# HDMI.net
KiCad netlist of a schematic drawn in Altium Designer
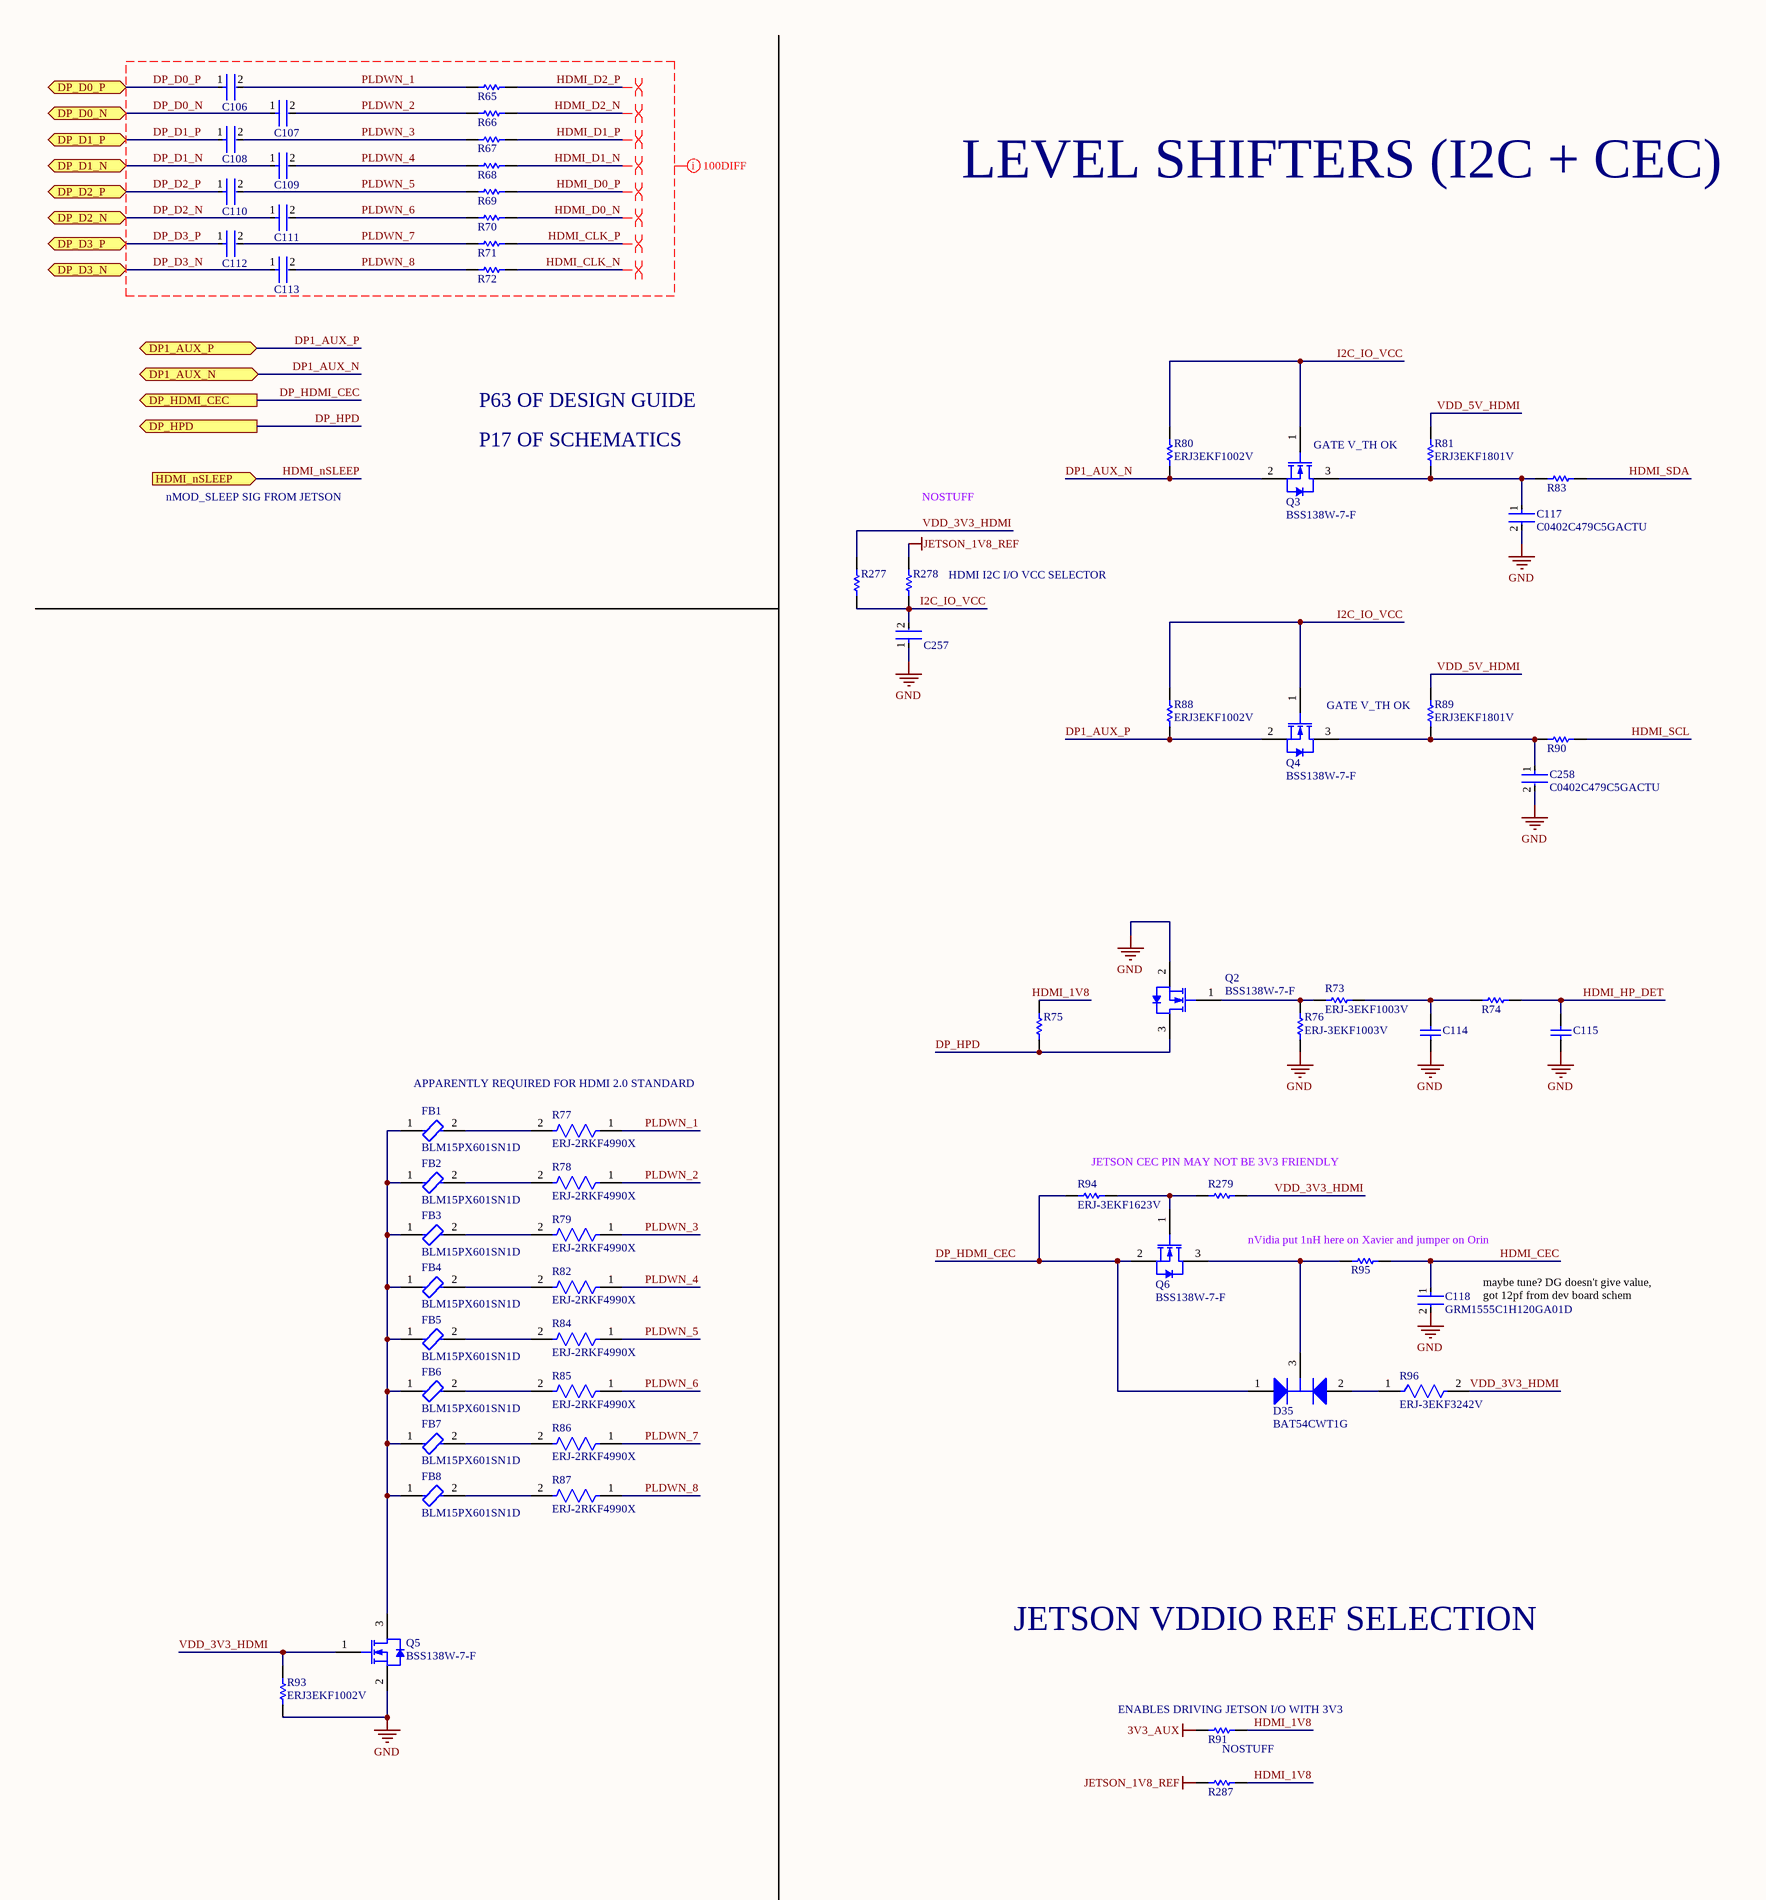
[diagram p0: HDMI.SchDoc, left]
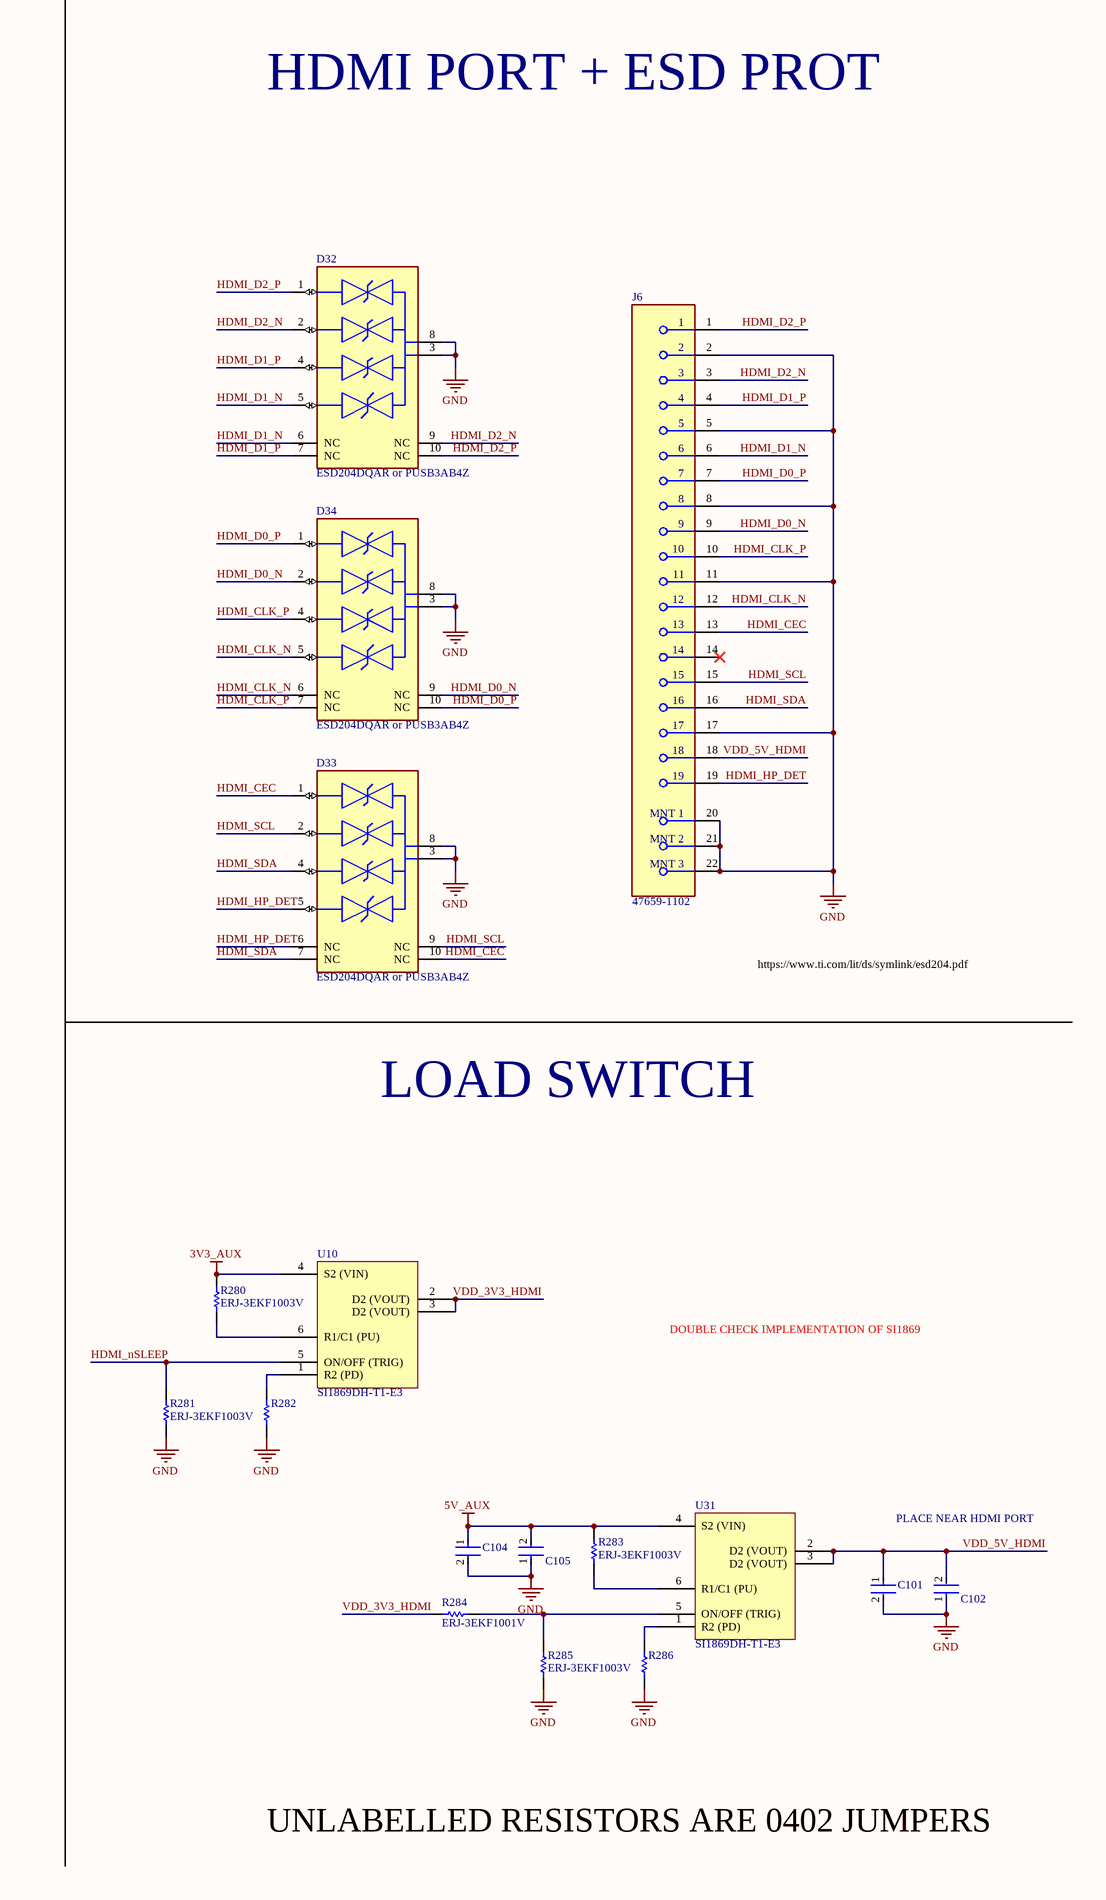
[diagram p1: HDMI.SchDoc, right]

(export (version "E")
  (design (tool "Eeschema 10.0.6"))
  (components
    (comp (ref "C101")
      (value "GRM188R60J106ME47D")
      (footprint "FP-GRM188-0_1-e0_2_0_55-IPC_A")
      (description "Chip Multilayer Ceramic Capacitors for General Purpose, 0603, 10uF, X5R, 15%, 20%, 6.3V")
      (fields (field (name "VOLTAGE") "6.3V") (field (name "TOLERANCE") "20%"))
      (libsource (lib "Altium Content Vault") (part "02cd4be3c70576c341d710602a673aa"))
    )
    (comp (ref "C102")
      (value "C1005X7R1H104K050BB")
      (footprint "FP-C1005-050-0_05-IPC_C")
      (description "Multilayer Ceramic Capacitors 100nF ±10% 50V X7R SMD 0402")
      (fields (field (name "VOLTAGE") "50V") (field (name "TOLERANCE") "10%"))
      (libsource (lib "Altium Content Vault") (part "b4654b650e69147ec39a6b967a45e02"))
    )
    (comp (ref "C104")
      (value "GRM188R60J106ME47D")
      (footprint "FP-GRM188-0_1-e0_2_0_55-IPC_A")
      (description "Chip Multilayer Ceramic Capacitors for General Purpose, 0603, 10uF, X5R, 15%, 20%, 6.3V")
      (fields (field (name "VOLTAGE") "6.3V") (field (name "TOLERANCE") "20%"))
      (libsource (lib "Altium Content Vault") (part "02cd4be3c70576c341d710602a673aa"))
    )
    (comp (ref "C105")
      (value "C1005X7R1H104K050BB")
      (footprint "FP-C1005-050-0_05-IPC_C")
      (description "Multilayer Ceramic Capacitors 100nF ±10% 50V X7R SMD 0402")
      (fields (field (name "VOLTAGE") "50V") (field (name "TOLERANCE") "10%"))
      (libsource (lib "Altium Content Vault") (part "b4654b650e69147ec39a6b967a45e02"))
    )
    (comp (ref "C106")
      (value "C1005X7R1H104K050BB")
      (footprint "FP-C1005-050-0_05-IPC_C")
      (description "Multilayer Ceramic Capacitors 100nF ±10% 50V X7R SMD 0402")
      (fields (field (name "VOLTAGE") "50V") (field (name "TOLERANCE") "10%"))
      (libsource (lib "Altium Content Vault") (part "b4654b650e69147ec39a6b967a45e02"))
    )
    (comp (ref "C107")
      (value "C1005X7R1H104K050BB")
      (footprint "FP-C1005-050-0_05-IPC_C")
      (description "Multilayer Ceramic Capacitors 100nF ±10% 50V X7R SMD 0402")
      (fields (field (name "VOLTAGE") "50V") (field (name "TOLERANCE") "10%"))
      (libsource (lib "Altium Content Vault") (part "b4654b650e69147ec39a6b967a45e02"))
    )
    (comp (ref "C108")
      (value "C1005X7R1H104K050BB")
      (footprint "FP-C1005-050-0_05-IPC_C")
      (description "Multilayer Ceramic Capacitors 100nF ±10% 50V X7R SMD 0402")
      (fields (field (name "VOLTAGE") "50V") (field (name "TOLERANCE") "10%"))
      (libsource (lib "Altium Content Vault") (part "b4654b650e69147ec39a6b967a45e02"))
    )
    (comp (ref "C109")
      (value "C1005X7R1H104K050BB")
      (footprint "FP-C1005-050-0_05-IPC_C")
      (description "Multilayer Ceramic Capacitors 100nF ±10% 50V X7R SMD 0402")
      (fields (field (name "VOLTAGE") "50V") (field (name "TOLERANCE") "10%"))
      (libsource (lib "Altium Content Vault") (part "b4654b650e69147ec39a6b967a45e02"))
    )
    (comp (ref "C110")
      (value "C1005X7R1H104K050BB")
      (footprint "FP-C1005-050-0_05-IPC_C")
      (description "Multilayer Ceramic Capacitors 100nF ±10% 50V X7R SMD 0402")
      (fields (field (name "VOLTAGE") "50V") (field (name "TOLERANCE") "10%"))
      (libsource (lib "Altium Content Vault") (part "b4654b650e69147ec39a6b967a45e02"))
    )
    (comp (ref "C111")
      (value "C1005X7R1H104K050BB")
      (footprint "FP-C1005-050-0_05-IPC_C")
      (description "Multilayer Ceramic Capacitors 100nF ±10% 50V X7R SMD 0402")
      (fields (field (name "VOLTAGE") "50V") (field (name "TOLERANCE") "10%"))
      (libsource (lib "Altium Content Vault") (part "b4654b650e69147ec39a6b967a45e02"))
    )
    (comp (ref "C112")
      (value "C1005X7R1H104K050BB")
      (footprint "FP-C1005-050-0_05-IPC_C")
      (description "Multilayer Ceramic Capacitors 100nF ±10% 50V X7R SMD 0402")
      (fields (field (name "VOLTAGE") "50V") (field (name "TOLERANCE") "10%"))
      (libsource (lib "Altium Content Vault") (part "b4654b650e69147ec39a6b967a45e02"))
    )
    (comp (ref "C113")
      (value "C1005X7R1H104K050BB")
      (footprint "FP-C1005-050-0_05-IPC_C")
      (description "Multilayer Ceramic Capacitors 100nF ±10% 50V X7R SMD 0402")
      (fields (field (name "VOLTAGE") "50V") (field (name "TOLERANCE") "10%"))
      (libsource (lib "Altium Content Vault") (part "b4654b650e69147ec39a6b967a45e02"))
    )
    (comp (ref "C114")
      (value "C0402C221K5RAC7867")
      (footprint "CAPC1005X60X30NL05T10")
      (fields (field (name "MANUFACTURER") "Kemet"))
      (libsource (lib "Altium Content Vault") (part "CAP"))
    )
    (comp (ref "C115")
      (value "C0402C221K5RAC7867")
      (footprint "CAPC1005X60X30NL05T10")
      (fields (field (name "MANUFACTURER") "Kemet"))
      (libsource (lib "Altium Content Vault") (part "CAP"))
    )
    (comp (ref "C117")
      (value "C0402C479C5GACTU")
      (footprint "FP-C0402-BB-MFG")
      (description "CAP CER 4.7PF 50V NP0 0402")
      (fields
        (field (name "TOLERANCE") "0.25 pF")
        (field (name "OCTOPART") "https://octopart.com/c0402c479c5gactu-kemet-9144199")
      )
      (libsource (lib "Altium Content Vault") (part "b4654b650e69147ec39a6b967a45e02"))
    )
    (comp (ref "C118")
      (value "GRM1555C1H120GA01D")
      (footprint "FP-GRM155-0_05-MFG")
      (description "CAP CER 12PF 50V C0G/NP0 0402")
      (fields (field (name "TOLERANCE") "2%") (field (name "VOLTAGE") "50V"))
      (libsource (lib "Altium Content Vault") (part "b4654b650e69147ec39a6b967a45e02"))
    )
    (comp (ref "C257")
      (value "C1005X7R1H104K050BB")
      (footprint "FP-C1005-050-0_05-IPC_C")
      (description "Multilayer Ceramic Capacitors 100nF ±10% 50V X7R SMD 0402")
      (fields (field (name "VOLTAGE") "50V") (field (name "TOLERANCE") "10%"))
      (libsource (lib "Altium Content Vault") (part "b4654b650e69147ec39a6b967a45e02"))
    )
    (comp (ref "C258")
      (value "C0402C479C5GACTU")
      (footprint "FP-C0402-BB-MFG")
      (description "CAP CER 4.7PF 50V NP0 0402")
      (fields
        (field (name "TOLERANCE") "0.25 pF")
        (field (name "OCTOPART") "https://octopart.com/c0402c479c5gactu-kemet-9144199")
      )
      (libsource (lib "Altium Content Vault") (part "b4654b650e69147ec39a6b967a45e02"))
    )
    (comp (ref "D32")
      (value "ESD204DQAR or PUSB3AB4Z")
      (footprint "FP-DQA0010A-MFG")
      (description "4-CHANNEL LOW-CAPACITANCE SURGE")
      (fields
        (field (name "MANUFACTURER") "Texas Instruments")
        (field (name "OCTOPART") "https://octopart.com/esd204dqar-texas+instruments-89917476")
      )
      (libsource (lib "Altium Content Vault") (part "1465e58c1818c7767b55926832f0bf5"))
    )
    (comp (ref "D33")
      (value "ESD204DQAR or PUSB3AB4Z")
      (footprint "FP-DQA0010A-MFG")
      (description "4-CHANNEL LOW-CAPACITANCE SURGE")
      (fields
        (field (name "MANUFACTURER") "Texas Instruments")
        (field (name "OCTOPART") "https://octopart.com/esd204dqar-texas+instruments-89917476")
      )
      (libsource (lib "Altium Content Vault") (part "1465e58c1818c7767b55926832f0bf5"))
    )
    (comp (ref "D34")
      (value "ESD204DQAR or PUSB3AB4Z")
      (footprint "FP-DQA0010A-MFG")
      (description "4-CHANNEL LOW-CAPACITANCE SURGE")
      (fields
        (field (name "MANUFACTURER") "Texas Instruments")
        (field (name "OCTOPART") "https://octopart.com/esd204dqar-texas+instruments-89917476")
      )
      (libsource (lib "Altium Content Vault") (part "1465e58c1818c7767b55926832f0bf5"))
    )
    (comp (ref "D35")
      (value "BAT54CWT1G")
      (footprint "ONSC-SOT-323-3-419-04_V")
      (description "Dual Series Cathode Schottky Barrier Diodes, 3-Pin SOT-323, Pb-Free, Tape and Reel")
      (fields (field (name "MANUFACTURER") "On Semiconductor"))
      (libsource (lib "Altium Content Vault") (part "ONSC-D-A1A2K3-3"))
    )
    (comp (ref "FB1")
      (value "BLM15PX601SN1D")
      (footprint "FP-BLM15-0_05-MFG")
      (description "Chip Ferrite Bead, 0402, 600Ω @ 100MHz, 0.23Ω, 25%, 900mA")
      (fields (field (name "TOLERANCE") "25%"))
      (libsource (lib "Altium Content Vault") (part "5f30dd21d616792df468990f7003faa"))
    )
    (comp (ref "FB2")
      (value "BLM15PX601SN1D")
      (footprint "FP-BLM15-0_05-MFG")
      (description "Chip Ferrite Bead, 0402, 600Ω @ 100MHz, 0.23Ω, 25%, 900mA")
      (fields (field (name "TOLERANCE") "25%"))
      (libsource (lib "Altium Content Vault") (part "5f30dd21d616792df468990f7003faa"))
    )
    (comp (ref "FB3")
      (value "BLM15PX601SN1D")
      (footprint "FP-BLM15-0_05-MFG")
      (description "Chip Ferrite Bead, 0402, 600Ω @ 100MHz, 0.23Ω, 25%, 900mA")
      (fields (field (name "TOLERANCE") "25%"))
      (libsource (lib "Altium Content Vault") (part "5f30dd21d616792df468990f7003faa"))
    )
    (comp (ref "FB4")
      (value "BLM15PX601SN1D")
      (footprint "FP-BLM15-0_05-MFG")
      (description "Chip Ferrite Bead, 0402, 600Ω @ 100MHz, 0.23Ω, 25%, 900mA")
      (fields (field (name "TOLERANCE") "25%"))
      (libsource (lib "Altium Content Vault") (part "5f30dd21d616792df468990f7003faa"))
    )
    (comp (ref "FB5")
      (value "BLM15PX601SN1D")
      (footprint "FP-BLM15-0_05-MFG")
      (description "Chip Ferrite Bead, 0402, 600Ω @ 100MHz, 0.23Ω, 25%, 900mA")
      (fields (field (name "TOLERANCE") "25%"))
      (libsource (lib "Altium Content Vault") (part "5f30dd21d616792df468990f7003faa"))
    )
    (comp (ref "FB6")
      (value "BLM15PX601SN1D")
      (footprint "FP-BLM15-0_05-MFG")
      (description "Chip Ferrite Bead, 0402, 600Ω @ 100MHz, 0.23Ω, 25%, 900mA")
      (fields (field (name "TOLERANCE") "25%"))
      (libsource (lib "Altium Content Vault") (part "5f30dd21d616792df468990f7003faa"))
    )
    (comp (ref "FB7")
      (value "BLM15PX601SN1D")
      (footprint "FP-BLM15-0_05-MFG")
      (description "Chip Ferrite Bead, 0402, 600Ω @ 100MHz, 0.23Ω, 25%, 900mA")
      (fields (field (name "TOLERANCE") "25%"))
      (libsource (lib "Altium Content Vault") (part "5f30dd21d616792df468990f7003faa"))
    )
    (comp (ref "FB8")
      (value "BLM15PX601SN1D")
      (footprint "FP-BLM15-0_05-MFG")
      (description "Chip Ferrite Bead, 0402, 600Ω @ 100MHz, 0.23Ω, 25%, 900mA")
      (fields (field (name "TOLERANCE") "25%"))
      (libsource (lib "Altium Content Vault") (part "5f30dd21d616792df468990f7003faa"))
    )
    (comp (ref "J6")
      (value "47659-1102")
      (footprint "FP-47659-1102-MFG")
      (description "HDMI REC.VERTICAL SMT TYPE W/HEI")
      (libsource (lib "Altium Content Vault") (part "60e05bcc1364a128ef07df4509dd673"))
    )
    (comp (ref "Q2")
      (value "BSS138W-7-F")
      (footprint "DIOD-SOT323-3_V")
      (fields (field (name "MANUFACTURER") "DiodesIncorporated"))
      (libsource (lib "Altium Content Vault") (part "NEMOS-GSD-3"))
    )
    (comp (ref "Q3")
      (value "BSS138W-7-F")
      (footprint "DIOD-SOT323-3_V")
      (fields (field (name "MANUFACTURER") "DiodesIncorporated"))
      (libsource (lib "Altium Content Vault") (part "NEMOS-GSD-3"))
    )
    (comp (ref "Q4")
      (value "BSS138W-7-F")
      (footprint "DIOD-SOT323-3_V")
      (fields (field (name "MANUFACTURER") "DiodesIncorporated"))
      (libsource (lib "Altium Content Vault") (part "NEMOS-GSD-3"))
    )
    (comp (ref "Q5")
      (value "BSS138W-7-F")
      (footprint "DIOD-SOT323-3_V")
      (fields (field (name "MANUFACTURER") "DiodesIncorporated"))
      (libsource (lib "Altium Content Vault") (part "NEMOS-GSD-3"))
    )
    (comp (ref "Q6")
      (value "BSS138W-7-F")
      (footprint "DIOD-SOT323-3_V")
      (fields (field (name "MANUFACTURER") "DiodesIncorporated"))
      (libsource (lib "Altium Content Vault") (part "NEMOS-GSD-3"))
    )
    (comp (ref "R65")
      (value "0402 JUMPER")
      (footprint "RESC1005X40X25ML05T05")
      (description "READ THE NAME")
      (libsource (lib "Space Concordia") (part "CMP-009-00206-2"))
    )
    (comp (ref "R66")
      (value "0402 JUMPER")
      (footprint "RESC1005X40X25ML05T05")
      (description "READ THE NAME")
      (libsource (lib "Space Concordia") (part "CMP-009-00206-2"))
    )
    (comp (ref "R67")
      (value "0402 JUMPER")
      (footprint "RESC1005X40X25ML05T05")
      (description "READ THE NAME")
      (libsource (lib "Space Concordia") (part "CMP-009-00206-2"))
    )
    (comp (ref "R68")
      (value "0402 JUMPER")
      (footprint "RESC1005X40X25ML05T05")
      (description "READ THE NAME")
      (libsource (lib "Space Concordia") (part "CMP-009-00206-2"))
    )
    (comp (ref "R69")
      (value "0402 JUMPER")
      (footprint "RESC1005X40X25ML05T05")
      (description "READ THE NAME")
      (libsource (lib "Space Concordia") (part "CMP-009-00206-2"))
    )
    (comp (ref "R70")
      (value "0402 JUMPER")
      (footprint "RESC1005X40X25ML05T05")
      (description "READ THE NAME")
      (libsource (lib "Space Concordia") (part "CMP-009-00206-2"))
    )
    (comp (ref "R71")
      (value "0402 JUMPER")
      (footprint "RESC1005X40X25ML05T05")
      (description "READ THE NAME")
      (libsource (lib "Space Concordia") (part "CMP-009-00206-2"))
    )
    (comp (ref "R72")
      (value "0402 JUMPER")
      (footprint "RESC1005X40X25ML05T05")
      (description "READ THE NAME")
      (libsource (lib "Space Concordia") (part "CMP-009-00206-2"))
    )
    (comp (ref "R73")
      (value "ERJ-3EKF1003V")
      (footprint "RESC1608X55X30ML15T15")
      (fields (field (name "MANUFACTURER") "Panasonic"))
      (libsource (lib "Altium Content Vault") (part "RES"))
    )
    (comp (ref "R74")
      (value "0402 JUMPER")
      (footprint "RESC1005X40X25ML05T05")
      (description "READ THE NAME")
      (libsource (lib "Space Concordia") (part "CMP-009-00206-2"))
    )
    (comp (ref "R75")
      (value "ERJ3EKF1002V")
      (footprint "RESC1609X55X30LL15T15")
      (description "Chip Resistor, 10 KOhm, +/- 1%, 0.1 W, -55 to 155 degC, 0603 (1608 Metric), RoHS, Tape and Reel")
      (fields (field (name "TOLERANCE") "1%") (field (name "MANUFACTURER") "Panasonic"))
      (libsource (lib "Altium Content Vault") (part "RES-2"))
    )
    (comp (ref "R76")
      (value "ERJ-3EKF1003V")
      (footprint "RESC1608X55X30ML15T15")
      (fields (field (name "MANUFACTURER") "Panasonic"))
      (libsource (lib "Altium Content Vault") (part "RES"))
    )
    (comp (ref "R77")
      (value "ERJ-2RKF4990X")
      (footprint "FP-ERJ2RK-MFG")
      (description "RES SMD 499 OHM 1% 1/10W 0402")
      (fields (field (name "TOLERANCE") "1%"))
      (libsource (lib "Altium Content Vault") (part "1029c3af85768c4190bb7ad29bc67b5"))
    )
    (comp (ref "R78")
      (value "ERJ-2RKF4990X")
      (footprint "FP-ERJ2RK-MFG")
      (description "RES SMD 499 OHM 1% 1/10W 0402")
      (fields (field (name "TOLERANCE") "1%"))
      (libsource (lib "Altium Content Vault") (part "1029c3af85768c4190bb7ad29bc67b5"))
    )
    (comp (ref "R79")
      (value "ERJ-2RKF4990X")
      (footprint "FP-ERJ2RK-MFG")
      (description "RES SMD 499 OHM 1% 1/10W 0402")
      (fields (field (name "TOLERANCE") "1%"))
      (libsource (lib "Altium Content Vault") (part "1029c3af85768c4190bb7ad29bc67b5"))
    )
    (comp (ref "R80")
      (value "ERJ3EKF1002V")
      (footprint "RESC1609X55X30LL15T15")
      (description "Chip Resistor, 10 KOhm, +/- 1%, 0.1 W, -55 to 155 degC, 0603 (1608 Metric), RoHS, Tape and Reel")
      (fields (field (name "TOLERANCE") "1%") (field (name "MANUFACTURER") "Panasonic"))
      (libsource (lib "Altium Content Vault") (part "RES-2"))
    )
    (comp (ref "R81")
      (value "ERJ3EKF1801V")
      (footprint "RESC1608X55X30LL15T15")
      (description "MODIFIED P/N")
      (fields (field (name "MANUFACTURER") "Panasonic") (field (name "PART NUMBER") "ERJ3EKF2701V"))
      (libsource (lib "Altium Content Vault") (part "RES"))
    )
    (comp (ref "R82")
      (value "ERJ-2RKF4990X")
      (footprint "FP-ERJ2RK-MFG")
      (description "RES SMD 499 OHM 1% 1/10W 0402")
      (fields (field (name "TOLERANCE") "1%"))
      (libsource (lib "Altium Content Vault") (part "1029c3af85768c4190bb7ad29bc67b5"))
    )
    (comp (ref "R83")
      (value "0402 JUMPER")
      (footprint "RESC1005X40X25ML05T05")
      (description "READ THE NAME")
      (libsource (lib "Space Concordia") (part "CMP-009-00206-2"))
    )
    (comp (ref "R84")
      (value "ERJ-2RKF4990X")
      (footprint "FP-ERJ2RK-MFG")
      (description "RES SMD 499 OHM 1% 1/10W 0402")
      (fields (field (name "TOLERANCE") "1%"))
      (libsource (lib "Altium Content Vault") (part "1029c3af85768c4190bb7ad29bc67b5"))
    )
    (comp (ref "R85")
      (value "ERJ-2RKF4990X")
      (footprint "FP-ERJ2RK-MFG")
      (description "RES SMD 499 OHM 1% 1/10W 0402")
      (fields (field (name "TOLERANCE") "1%"))
      (libsource (lib "Altium Content Vault") (part "1029c3af85768c4190bb7ad29bc67b5"))
    )
    (comp (ref "R86")
      (value "ERJ-2RKF4990X")
      (footprint "FP-ERJ2RK-MFG")
      (description "RES SMD 499 OHM 1% 1/10W 0402")
      (fields (field (name "TOLERANCE") "1%"))
      (libsource (lib "Altium Content Vault") (part "1029c3af85768c4190bb7ad29bc67b5"))
    )
    (comp (ref "R87")
      (value "ERJ-2RKF4990X")
      (footprint "FP-ERJ2RK-MFG")
      (description "RES SMD 499 OHM 1% 1/10W 0402")
      (fields (field (name "TOLERANCE") "1%"))
      (libsource (lib "Altium Content Vault") (part "1029c3af85768c4190bb7ad29bc67b5"))
    )
    (comp (ref "R88")
      (value "ERJ3EKF1002V")
      (footprint "RESC1609X55X30LL15T15")
      (description "Chip Resistor, 10 KOhm, +/- 1%, 0.1 W, -55 to 155 degC, 0603 (1608 Metric), RoHS, Tape and Reel")
      (fields (field (name "TOLERANCE") "1%") (field (name "MANUFACTURER") "Panasonic"))
      (libsource (lib "Altium Content Vault") (part "RES-2"))
    )
    (comp (ref "R89")
      (value "ERJ3EKF1801V")
      (footprint "RESC1608X55X30LL15T15")
      (description "MODIFIED P/N")
      (fields (field (name "MANUFACTURER") "Panasonic") (field (name "PART NUMBER") "ERJ3EKF2701V"))
      (libsource (lib "Altium Content Vault") (part "RES"))
    )
    (comp (ref "R90")
      (value "0402 JUMPER")
      (footprint "RESC1005X40X25ML05T05")
      (description "READ THE NAME")
      (libsource (lib "Space Concordia") (part "CMP-009-00206-2"))
    )
    (comp (ref "R91")
      (value "0402 JUMPER")
      (footprint "RESC1005X40X25ML05T05")
      (description "READ THE NAME")
      (libsource (lib "Space Concordia") (part "CMP-009-00206-2"))
    )
    (comp (ref "R93")
      (value "ERJ3EKF1002V")
      (footprint "RESC1609X55X30LL15T15")
      (description "Chip Resistor, 10 KOhm, +/- 1%, 0.1 W, -55 to 155 degC, 0603 (1608 Metric), RoHS, Tape and Reel")
      (fields (field (name "TOLERANCE") "1%") (field (name "MANUFACTURER") "Panasonic"))
      (libsource (lib "Altium Content Vault") (part "RES-2"))
    )
    (comp (ref "R94")
      (value "ERJ-3EKF1623V")
      (footprint "RESC1608X55X30ML15T15")
      (fields (field (name "MANUFACTURER") "Panasonic"))
      (libsource (lib "Altium Content Vault") (part "RES"))
    )
    (comp (ref "R95")
      (value "0402 JUMPER")
      (footprint "RESC1005X40X25ML05T05")
      (description "READ THE NAME")
      (libsource (lib "Space Concordia") (part "CMP-009-00206-2"))
    )
    (comp (ref "R96")
      (value "ERJ-3EKF3242V")
      (footprint "FP-ERJ3EK-MFG")
      (description "RES SMD 32.4K OHM 1% 1/10W 0603")
      (fields (field (name "TOLERANCE") "1%"))
      (libsource (lib "Altium Content Vault") (part "1029c3af85768c4190bb7ad29bc67b5"))
    )
    (comp (ref "R277")
      (value "0402 JUMPER")
      (footprint "RESC1005X40X25ML05T05")
      (description "READ THE NAME")
      (libsource (lib "Space Concordia") (part "CMP-009-00206-2"))
    )
    (comp (ref "R278")
      (value "0402 JUMPER")
      (footprint "RESC1005X40X25ML05T05")
      (description "READ THE NAME")
      (libsource (lib "Space Concordia") (part "CMP-009-00206-2"))
    )
    (comp (ref "R279")
      (value "0402 JUMPER")
      (footprint "RESC1005X40X25ML05T05")
      (description "READ THE NAME")
      (libsource (lib "Space Concordia") (part "CMP-009-00206-2"))
    )
    (comp (ref "R280")
      (value "ERJ-3EKF1003V")
      (footprint "RESC1608X55X30ML15T15")
      (fields (field (name "MANUFACTURER") "Panasonic"))
      (libsource (lib "Altium Content Vault") (part "RES"))
    )
    (comp (ref "R281")
      (value "ERJ-3EKF1003V")
      (footprint "RESC1608X55X30ML15T15")
      (fields (field (name "MANUFACTURER") "Panasonic"))
      (libsource (lib "Altium Content Vault") (part "RES"))
    )
    (comp (ref "R282")
      (value "0402 JUMPER")
      (footprint "RESC1005X40X25ML05T05")
      (description "READ THE NAME")
      (libsource (lib "Space Concordia") (part "CMP-009-00206-2"))
    )
    (comp (ref "R283")
      (value "ERJ-3EKF1003V")
      (footprint "RESC1608X55X30ML15T15")
      (fields (field (name "MANUFACTURER") "Panasonic"))
      (libsource (lib "Altium Content Vault") (part "RES"))
    )
    (comp (ref "R284")
      (value "ERJ-3EKF1001V")
      (footprint "RESC1608X55X30LL15T15")
      (fields (field (name "MANUFACTURER") "Panasonic"))
      (libsource (lib "Altium Content Vault") (part "RES"))
    )
    (comp (ref "R285")
      (value "ERJ-3EKF1003V")
      (footprint "RESC1608X55X30ML15T15")
      (fields (field (name "MANUFACTURER") "Panasonic"))
      (libsource (lib "Altium Content Vault") (part "RES"))
    )
    (comp (ref "R286")
      (value "0402 JUMPER")
      (footprint "RESC1005X40X25ML05T05")
      (description "READ THE NAME")
      (libsource (lib "Space Concordia") (part "CMP-009-00206-2"))
    )
    (comp (ref "R287")
      (value "0402 JUMPER")
      (footprint "RESC1005X40X25ML05T05")
      (description "READ THE NAME")
      (libsource (lib "Space Concordia") (part "CMP-009-00206-2"))
    )
    (comp (ref "U10")
      (value "SI1869DH-T1-E3")
      (footprint "SOT65P242X110-6N")
      (description "Power Supply Support Circuit, Adjustable, 1 Channel, PDSO6")
      (libsource (lib "Space Concordia") (part "SI1869DH-T1-E3"))
    )
    (comp (ref "U31")
      (value "SI1869DH-T1-E3")
      (footprint "SOT65P242X110-6N")
      (description "Power Supply Support Circuit, Adjustable, 1 Channel, PDSO6")
      (libsource (lib "Space Concordia") (part "SI1869DH-T1-E3"))
    )
  )
  (nets
    (net (code "1") (name "/DP1_AUX_N") (class "Default")
      (node (ref "Q3") (pin "2") (pinfunction "S_2") (pintype "passive"))
      (node (ref "R80") (pin "1") (pinfunction "1_1") (pintype "passive"))
    )
    (net (code "2") (name "/DP1_AUX_P") (class "Default")
      (node (ref "Q4") (pin "2") (pinfunction "S_2") (pintype "passive"))
      (node (ref "R88") (pin "1") (pinfunction "1_1") (pintype "passive"))
    )
    (net (code "3") (name "/DP_D0_N") (class "Default")
      (node (ref "C107") (pin "1") (pinfunction "1_1") (pintype "passive"))
    )
    (net (code "4") (name "/DP_D0_P") (class "Default")
      (node (ref "C106") (pin "1") (pinfunction "1_1") (pintype "passive"))
    )
    (net (code "5") (name "/DP_D1_N") (class "Default")
      (node (ref "C109") (pin "1") (pinfunction "1_1") (pintype "passive"))
    )
    (net (code "6") (name "/DP_D1_P") (class "Default")
      (node (ref "C108") (pin "1") (pinfunction "1_1") (pintype "passive"))
    )
    (net (code "7") (name "/DP_D2_N") (class "Default")
      (node (ref "C111") (pin "1") (pinfunction "1_1") (pintype "passive"))
    )
    (net (code "8") (name "/DP_D2_P") (class "Default")
      (node (ref "C110") (pin "1") (pinfunction "1_1") (pintype "passive"))
    )
    (net (code "9") (name "/DP_D3_N") (class "Default")
      (node (ref "C113") (pin "1") (pinfunction "1_1") (pintype "passive"))
    )
    (net (code "10") (name "/DP_D3_P") (class "Default")
      (node (ref "C112") (pin "1") (pinfunction "1_1") (pintype "passive"))
    )
    (net (code "11") (name "/DP_HDMI_CEC") (class "Default")
      (node (ref "D35") (pin "1") (pinfunction "A1_1") (pintype "passive"))
      (node (ref "Q6") (pin "2") (pinfunction "S_2") (pintype "passive"))
      (node (ref "R94") (pin "1") (pinfunction "1_1") (pintype "passive"))
    )
    (net (code "12") (name "/DP_HPD") (class "Default")
      (node (ref "Q2") (pin "3") (pinfunction "D_3") (pintype "passive"))
      (node (ref "R75") (pin "1") (pinfunction "1_1") (pintype "passive"))
    )
    (net (code "13") (name "/HDMI_1V8") (class "Default")
      (node (ref "R287") (pin "2") (pinfunction "2_2") (pintype "passive"))
      (node (ref "R75") (pin "2") (pinfunction "2_2") (pintype "passive"))
      (node (ref "R91") (pin "2") (pinfunction "2_2") (pintype "passive"))
    )
    (net (code "14") (name "/HDMI_CEC") (class "Default")
      (node (ref "C118") (pin "1") (pinfunction "1_1") (pintype "passive"))
      (node (ref "D33") (pin "1") (pinfunction "IO1_1") (pintype "bidirectional"))
      (node (ref "D33") (pin "10") (pinfunction "NC_10") (pintype "passive"))
      (node (ref "J6") (pin "13") (pinfunction "13_13") (pintype "passive"))
      (node (ref "R95") (pin "2") (pinfunction "2_2") (pintype "passive"))
    )
    (net (code "15") (name "/HDMI_CLK_N") (class "Default")
      (node (ref "D34") (pin "5") (pinfunction "IO4_5") (pintype "bidirectional"))
      (node (ref "D34") (pin "6") (pinfunction "NC_6") (pintype "passive"))
      (node (ref "J6") (pin "12") (pinfunction "12_12") (pintype "passive"))
      (node (ref "R72") (pin "2") (pinfunction "2_2") (pintype "passive"))
    )
    (net (code "16") (name "/HDMI_CLK_P") (class "Default")
      (node (ref "D34") (pin "4") (pinfunction "IO3_4") (pintype "bidirectional"))
      (node (ref "D34") (pin "7") (pinfunction "NC_7") (pintype "passive"))
      (node (ref "J6") (pin "10") (pinfunction "10_10") (pintype "passive"))
      (node (ref "R71") (pin "2") (pinfunction "2_2") (pintype "passive"))
    )
    (net (code "17") (name "/HDMI_D0_N") (class "Default")
      (node (ref "D34") (pin "2") (pinfunction "IO2_2") (pintype "bidirectional"))
      (node (ref "D34") (pin "9") (pinfunction "NC_9") (pintype "passive"))
      (node (ref "J6") (pin "9") (pinfunction "9_9") (pintype "passive"))
      (node (ref "R70") (pin "2") (pinfunction "2_2") (pintype "passive"))
    )
    (net (code "18") (name "/HDMI_D0_P") (class "Default")
      (node (ref "D34") (pin "1") (pinfunction "IO1_1") (pintype "bidirectional"))
      (node (ref "D34") (pin "10") (pinfunction "NC_10") (pintype "passive"))
      (node (ref "J6") (pin "7") (pinfunction "7_7") (pintype "passive"))
      (node (ref "R69") (pin "2") (pinfunction "2_2") (pintype "passive"))
    )
    (net (code "19") (name "/HDMI_D1_N") (class "Default")
      (node (ref "D32") (pin "5") (pinfunction "IO4_5") (pintype "bidirectional"))
      (node (ref "D32") (pin "6") (pinfunction "NC_6") (pintype "passive"))
      (node (ref "J6") (pin "6") (pinfunction "6_6") (pintype "passive"))
      (node (ref "R68") (pin "2") (pinfunction "2_2") (pintype "passive"))
    )
    (net (code "20") (name "/HDMI_D1_P") (class "Default")
      (node (ref "D32") (pin "4") (pinfunction "IO3_4") (pintype "bidirectional"))
      (node (ref "D32") (pin "7") (pinfunction "NC_7") (pintype "passive"))
      (node (ref "J6") (pin "4") (pinfunction "4_4") (pintype "passive"))
      (node (ref "R67") (pin "2") (pinfunction "2_2") (pintype "passive"))
    )
    (net (code "21") (name "/HDMI_D2_N") (class "Default")
      (node (ref "D32") (pin "2") (pinfunction "IO2_2") (pintype "bidirectional"))
      (node (ref "D32") (pin "9") (pinfunction "NC_9") (pintype "passive"))
      (node (ref "J6") (pin "3") (pinfunction "3_3") (pintype "passive"))
      (node (ref "R66") (pin "2") (pinfunction "2_2") (pintype "passive"))
    )
    (net (code "22") (name "/HDMI_D2_P") (class "Default")
      (node (ref "D32") (pin "1") (pinfunction "IO1_1") (pintype "bidirectional"))
      (node (ref "D32") (pin "10") (pinfunction "NC_10") (pintype "passive"))
      (node (ref "J6") (pin "1") (pinfunction "1_1") (pintype "passive"))
      (node (ref "R65") (pin "2") (pinfunction "2_2") (pintype "passive"))
    )
    (net (code "23") (name "/HDMI_HP_DET") (class "Default")
      (node (ref "C115") (pin "2") (pinfunction "2_2") (pintype "passive"))
      (node (ref "D33") (pin "5") (pinfunction "IO4_5") (pintype "bidirectional"))
      (node (ref "D33") (pin "6") (pinfunction "NC_6") (pintype "passive"))
      (node (ref "J6") (pin "19") (pinfunction "19_19") (pintype "passive"))
      (node (ref "R74") (pin "2") (pinfunction "2_2") (pintype "passive"))
    )
    (net (code "24") (name "/HDMI_SCL") (class "Default")
      (node (ref "D33") (pin "2") (pinfunction "IO2_2") (pintype "bidirectional"))
      (node (ref "D33") (pin "9") (pinfunction "NC_9") (pintype "passive"))
      (node (ref "J6") (pin "15") (pinfunction "15_15") (pintype "passive"))
      (node (ref "R90") (pin "2") (pinfunction "2_2") (pintype "passive"))
    )
    (net (code "25") (name "/HDMI_SDA") (class "Default")
      (node (ref "D33") (pin "4") (pinfunction "IO3_4") (pintype "bidirectional"))
      (node (ref "D33") (pin "7") (pinfunction "NC_7") (pintype "passive"))
      (node (ref "J6") (pin "16") (pinfunction "16_16") (pintype "passive"))
      (node (ref "R83") (pin "2") (pinfunction "2_2") (pintype "passive"))
    )
    (net (code "26") (name "/HDMI_nSLEEP") (class "Default")
      (node (ref "R281") (pin "2") (pinfunction "2_2") (pintype "passive"))
      (node (ref "U10") (pin "5") (pinfunction "ON/OFF_(TRIG)_5") (pintype "passive"))
    )
    (net (code "27") (name "/I2C_IO_VCC") (class "Default")
      (node (ref "C257") (pin "2") (pinfunction "2_2") (pintype "passive"))
      (node (ref "Q3") (pin "1") (pinfunction "G_1") (pintype "passive"))
      (node (ref "Q4") (pin "1") (pinfunction "G_1") (pintype "passive"))
      (node (ref "R277") (pin "1") (pinfunction "1_1") (pintype "passive"))
      (node (ref "R278") (pin "1") (pinfunction "1_1") (pintype "passive"))
      (node (ref "R80") (pin "2") (pinfunction "2_2") (pintype "passive"))
      (node (ref "R88") (pin "2") (pinfunction "2_2") (pintype "passive"))
    )
    (net (code "28") (name "/PLDWN_1") (class "Default")
      (node (ref "C106") (pin "2") (pinfunction "2_2") (pintype "passive"))
      (node (ref "R65") (pin "1") (pinfunction "1_1") (pintype "passive"))
      (node (ref "R77") (pin "1") (pinfunction "1_1") (pintype "passive"))
    )
    (net (code "29") (name "/PLDWN_2") (class "Default")
      (node (ref "C107") (pin "2") (pinfunction "2_2") (pintype "passive"))
      (node (ref "R66") (pin "1") (pinfunction "1_1") (pintype "passive"))
      (node (ref "R78") (pin "1") (pinfunction "1_1") (pintype "passive"))
    )
    (net (code "30") (name "/PLDWN_3") (class "Default")
      (node (ref "C108") (pin "2") (pinfunction "2_2") (pintype "passive"))
      (node (ref "R67") (pin "1") (pinfunction "1_1") (pintype "passive"))
      (node (ref "R79") (pin "1") (pinfunction "1_1") (pintype "passive"))
    )
    (net (code "31") (name "/PLDWN_4") (class "Default")
      (node (ref "C109") (pin "2") (pinfunction "2_2") (pintype "passive"))
      (node (ref "R68") (pin "1") (pinfunction "1_1") (pintype "passive"))
      (node (ref "R82") (pin "1") (pinfunction "1_1") (pintype "passive"))
    )
    (net (code "32") (name "/PLDWN_5") (class "Default")
      (node (ref "C110") (pin "2") (pinfunction "2_2") (pintype "passive"))
      (node (ref "R69") (pin "1") (pinfunction "1_1") (pintype "passive"))
      (node (ref "R84") (pin "1") (pinfunction "1_1") (pintype "passive"))
    )
    (net (code "33") (name "/PLDWN_6") (class "Default")
      (node (ref "C111") (pin "2") (pinfunction "2_2") (pintype "passive"))
      (node (ref "R70") (pin "1") (pinfunction "1_1") (pintype "passive"))
      (node (ref "R85") (pin "1") (pinfunction "1_1") (pintype "passive"))
    )
    (net (code "34") (name "/PLDWN_7") (class "Default")
      (node (ref "C112") (pin "2") (pinfunction "2_2") (pintype "passive"))
      (node (ref "R71") (pin "1") (pinfunction "1_1") (pintype "passive"))
      (node (ref "R86") (pin "1") (pinfunction "1_1") (pintype "passive"))
    )
    (net (code "35") (name "/PLDWN_8") (class "Default")
      (node (ref "C113") (pin "2") (pinfunction "2_2") (pintype "passive"))
      (node (ref "R72") (pin "1") (pinfunction "1_1") (pintype "passive"))
      (node (ref "R87") (pin "1") (pinfunction "1_1") (pintype "passive"))
    )
    (net (code "36") (name "/VDD_3V3_HDMI") (class "Default")
      (node (ref "Q5") (pin "1") (pinfunction "G_1") (pintype "passive"))
      (node (ref "R277") (pin "2") (pinfunction "2_2") (pintype "passive"))
      (node (ref "R279") (pin "1") (pinfunction "1_1") (pintype "passive"))
      (node (ref "R284") (pin "1") (pinfunction "1_1") (pintype "passive"))
      (node (ref "R93") (pin "2") (pinfunction "2_2") (pintype "passive"))
      (node (ref "R96") (pin "2") (pinfunction "2_2") (pintype "passive"))
      (node (ref "U10") (pin "2") (pinfunction "D2_(VOUT)_2") (pintype "passive"))
      (node (ref "U10") (pin "3") (pinfunction "D2_(VOUT)_3") (pintype "passive"))
    )
    (net (code "37") (name "/VDD_5V_HDMI") (class "Default")
      (node (ref "C101") (pin "1") (pinfunction "1_1") (pintype "passive"))
      (node (ref "C102") (pin "2") (pinfunction "2_2") (pintype "passive"))
      (node (ref "J6") (pin "18") (pinfunction "18_18") (pintype "passive"))
      (node (ref "R81") (pin "2") (pinfunction "2_2") (pintype "passive"))
      (node (ref "R89") (pin "2") (pinfunction "2_2") (pintype "passive"))
      (node (ref "U31") (pin "2") (pinfunction "D2_(VOUT)_2") (pintype "passive"))
      (node (ref "U31") (pin "3") (pinfunction "D2_(VOUT)_3") (pintype "passive"))
    )
    (net (code "38") (name "3V3_AUX") (class "Default")
      (node (ref "R280") (pin "2") (pinfunction "2_2") (pintype "passive"))
      (node (ref "R91") (pin "1") (pinfunction "1_1") (pintype "passive"))
      (node (ref "U10") (pin "4") (pinfunction "S2_(VIN)_4") (pintype "passive"))
    )
    (net (code "39") (name "5V_AUX") (class "Default")
      (node (ref "C104") (pin "1") (pinfunction "1_1") (pintype "passive"))
      (node (ref "C105") (pin "2") (pinfunction "2_2") (pintype "passive"))
      (node (ref "R283") (pin "2") (pinfunction "2_2") (pintype "passive"))
      (node (ref "U31") (pin "4") (pinfunction "S2_(VIN)_4") (pintype "passive"))
    )
    (net (code "40") (name "GND") (class "Default")
      (node (ref "C101") (pin "2") (pinfunction "2_2") (pintype "passive"))
      (node (ref "C102") (pin "1") (pinfunction "1_1") (pintype "passive"))
      (node (ref "C104") (pin "2") (pinfunction "2_2") (pintype "passive"))
      (node (ref "C105") (pin "1") (pinfunction "1_1") (pintype "passive"))
      (node (ref "C114") (pin "1") (pinfunction "1_1") (pintype "passive"))
      (node (ref "C115") (pin "1") (pinfunction "1_1") (pintype "passive"))
      (node (ref "C117") (pin "2") (pinfunction "2_2") (pintype "passive"))
      (node (ref "C118") (pin "2") (pinfunction "2_2") (pintype "passive"))
      (node (ref "C257") (pin "1") (pinfunction "1_1") (pintype "passive"))
      (node (ref "C258") (pin "2") (pinfunction "2_2") (pintype "passive"))
      (node (ref "D32") (pin "3") (pinfunction "GND_3") (pintype "power_in"))
      (node (ref "D32") (pin "8") (pinfunction "GND_8") (pintype "power_in"))
      (node (ref "D33") (pin "3") (pinfunction "GND_3") (pintype "power_in"))
      (node (ref "D33") (pin "8") (pinfunction "GND_8") (pintype "power_in"))
      (node (ref "D34") (pin "3") (pinfunction "GND_3") (pintype "power_in"))
      (node (ref "D34") (pin "8") (pinfunction "GND_8") (pintype "power_in"))
      (node (ref "J6") (pin "11") (pinfunction "11_11") (pintype "passive"))
      (node (ref "J6") (pin "17") (pinfunction "17_17") (pintype "passive"))
      (node (ref "J6") (pin "2") (pinfunction "2_2") (pintype "passive"))
      (node (ref "J6") (pin "20") (pinfunction "MNT_1_20") (pintype "passive"))
      (node (ref "J6") (pin "21") (pinfunction "MNT_2_21") (pintype "passive"))
      (node (ref "J6") (pin "22") (pinfunction "MNT_3_22") (pintype "passive"))
      (node (ref "J6") (pin "5") (pinfunction "5_5") (pintype "passive"))
      (node (ref "J6") (pin "8") (pinfunction "8_8") (pintype "passive"))
      (node (ref "Q2") (pin "2") (pinfunction "S_2") (pintype "passive"))
      (node (ref "Q5") (pin "2") (pinfunction "S_2") (pintype "passive"))
      (node (ref "R281") (pin "1") (pinfunction "1_1") (pintype "passive"))
      (node (ref "R282") (pin "2") (pinfunction "2_2") (pintype "passive"))
      (node (ref "R285") (pin "1") (pinfunction "1_1") (pintype "passive"))
      (node (ref "R286") (pin "2") (pinfunction "2_2") (pintype "passive"))
      (node (ref "R76") (pin "1") (pinfunction "1_1") (pintype "passive"))
      (node (ref "R93") (pin "1") (pinfunction "1_1") (pintype "passive"))
    )
    (net (code "41") (name "JETSON_1V8_REF") (class "Default")
      (node (ref "R278") (pin "2") (pinfunction "2_2") (pintype "passive"))
      (node (ref "R287") (pin "1") (pinfunction "1_1") (pintype "passive"))
    )
    (net (code "42") (name "Net-(C114-Pad2)") (class "Default")
      (node (ref "C114") (pin "2") (pinfunction "2_2") (pintype "passive"))
      (node (ref "R73") (pin "2") (pinfunction "2_2") (pintype "passive"))
      (node (ref "R74") (pin "1") (pinfunction "1_1") (pintype "passive"))
    )
    (net (code "43") (name "Net-(D35-A2)") (class "Default")
      (node (ref "D35") (pin "2") (pinfunction "A2_2") (pintype "passive"))
      (node (ref "R96") (pin "1") (pinfunction "1_1") (pintype "passive"))
    )
    (net (code "44") (name "Net-(D35-K)") (class "Default")
      (node (ref "D35") (pin "3") (pinfunction "K_3") (pintype "passive"))
      (node (ref "Q6") (pin "3") (pinfunction "D_3") (pintype "passive"))
      (node (ref "R95") (pin "1") (pinfunction "1_1") (pintype "passive"))
    )
    (net (code "45") (name "Net-(FB1-Pad2)") (class "Default")
      (node (ref "FB1") (pin "2") (pinfunction "2_2") (pintype "passive"))
      (node (ref "R77") (pin "2") (pinfunction "2_2") (pintype "passive"))
    )
    (net (code "46") (name "Net-(FB2-Pad2)") (class "Default")
      (node (ref "FB2") (pin "2") (pinfunction "2_2") (pintype "passive"))
      (node (ref "R78") (pin "2") (pinfunction "2_2") (pintype "passive"))
    )
    (net (code "47") (name "Net-(FB3-Pad2)") (class "Default")
      (node (ref "FB3") (pin "2") (pinfunction "2_2") (pintype "passive"))
      (node (ref "R79") (pin "2") (pinfunction "2_2") (pintype "passive"))
    )
    (net (code "48") (name "Net-(FB4-Pad2)") (class "Default")
      (node (ref "FB4") (pin "2") (pinfunction "2_2") (pintype "passive"))
      (node (ref "R82") (pin "2") (pinfunction "2_2") (pintype "passive"))
    )
    (net (code "49") (name "Net-(FB5-Pad2)") (class "Default")
      (node (ref "FB5") (pin "2") (pinfunction "2_2") (pintype "passive"))
      (node (ref "R84") (pin "2") (pinfunction "2_2") (pintype "passive"))
    )
    (net (code "50") (name "Net-(FB6-Pad2)") (class "Default")
      (node (ref "FB6") (pin "2") (pinfunction "2_2") (pintype "passive"))
      (node (ref "R85") (pin "2") (pinfunction "2_2") (pintype "passive"))
    )
    (net (code "51") (name "Net-(FB7-Pad2)") (class "Default")
      (node (ref "FB7") (pin "2") (pinfunction "2_2") (pintype "passive"))
      (node (ref "R86") (pin "2") (pinfunction "2_2") (pintype "passive"))
    )
    (net (code "52") (name "Net-(FB8-Pad2)") (class "Default")
      (node (ref "FB8") (pin "2") (pinfunction "2_2") (pintype "passive"))
      (node (ref "R87") (pin "2") (pinfunction "2_2") (pintype "passive"))
    )
    (net (code "53") (name "Net-(Q2-G)") (class "Default")
      (node (ref "Q2") (pin "1") (pinfunction "G_1") (pintype "passive"))
      (node (ref "R73") (pin "1") (pinfunction "1_1") (pintype "passive"))
      (node (ref "R76") (pin "2") (pinfunction "2_2") (pintype "passive"))
    )
    (net (code "54") (name "Net-(Q3-D)") (class "Default")
      (node (ref "C117") (pin "1") (pinfunction "1_1") (pintype "passive"))
      (node (ref "Q3") (pin "3") (pinfunction "D_3") (pintype "passive"))
      (node (ref "R81") (pin "1") (pinfunction "1_1") (pintype "passive"))
      (node (ref "R83") (pin "1") (pinfunction "1_1") (pintype "passive"))
    )
    (net (code "55") (name "Net-(Q4-D)") (class "Default")
      (node (ref "C258") (pin "1") (pinfunction "1_1") (pintype "passive"))
      (node (ref "Q4") (pin "3") (pinfunction "D_3") (pintype "passive"))
      (node (ref "R89") (pin "1") (pinfunction "1_1") (pintype "passive"))
      (node (ref "R90") (pin "1") (pinfunction "1_1") (pintype "passive"))
    )
    (net (code "56") (name "Net-(Q5-D)") (class "Default")
      (node (ref "FB1") (pin "1") (pinfunction "1_1") (pintype "passive"))
      (node (ref "FB2") (pin "1") (pinfunction "1_1") (pintype "passive"))
      (node (ref "FB3") (pin "1") (pinfunction "1_1") (pintype "passive"))
      (node (ref "FB4") (pin "1") (pinfunction "1_1") (pintype "passive"))
      (node (ref "FB5") (pin "1") (pinfunction "1_1") (pintype "passive"))
      (node (ref "FB6") (pin "1") (pinfunction "1_1") (pintype "passive"))
      (node (ref "FB7") (pin "1") (pinfunction "1_1") (pintype "passive"))
      (node (ref "FB8") (pin "1") (pinfunction "1_1") (pintype "passive"))
      (node (ref "Q5") (pin "3") (pinfunction "D_3") (pintype "passive"))
    )
    (net (code "57") (name "Net-(Q6-G)") (class "Default")
      (node (ref "Q6") (pin "1") (pinfunction "G_1") (pintype "passive"))
      (node (ref "R279") (pin "2") (pinfunction "2_2") (pintype "passive"))
      (node (ref "R94") (pin "2") (pinfunction "2_2") (pintype "passive"))
    )
    (net (code "58") (name "Net-(U10-R1{slash}C1_(PU))") (class "Default")
      (node (ref "R280") (pin "1") (pinfunction "1_1") (pintype "passive"))
      (node (ref "U10") (pin "6") (pinfunction "R1/C1_(PU)_6") (pintype "passive"))
    )
    (net (code "59") (name "Net-(U10-R2_(PD))") (class "Default")
      (node (ref "R282") (pin "1") (pinfunction "1_1") (pintype "passive"))
      (node (ref "U10") (pin "1") (pinfunction "R2_(PD)_1") (pintype "passive"))
    )
    (net (code "60") (name "Net-(U31-ON{slash}OFF_(TRIG))") (class "Default")
      (node (ref "R284") (pin "2") (pinfunction "2_2") (pintype "passive"))
      (node (ref "R285") (pin "2") (pinfunction "2_2") (pintype "passive"))
      (node (ref "U31") (pin "5") (pinfunction "ON/OFF_(TRIG)_5") (pintype "passive"))
    )
    (net (code "61") (name "Net-(U31-R1{slash}C1_(PU))") (class "Default")
      (node (ref "R283") (pin "1") (pinfunction "1_1") (pintype "passive"))
      (node (ref "U31") (pin "6") (pinfunction "R1/C1_(PU)_6") (pintype "passive"))
    )
    (net (code "62") (name "Net-(U31-R2_(PD))") (class "Default")
      (node (ref "R286") (pin "1") (pinfunction "1_1") (pintype "passive"))
      (node (ref "U31") (pin "1") (pinfunction "R2_(PD)_1") (pintype "passive"))
    )
    (net (code "63") (name "unconnected-(J6-Pad14)") (class "Default")
      (node (ref "J6") (pin "14") (pinfunction "14_14") (pintype "passive+no_connect"))
    )
  )
)
